# coil_processing.net
KiCad netlist of a schematic drawn in Altium Designer
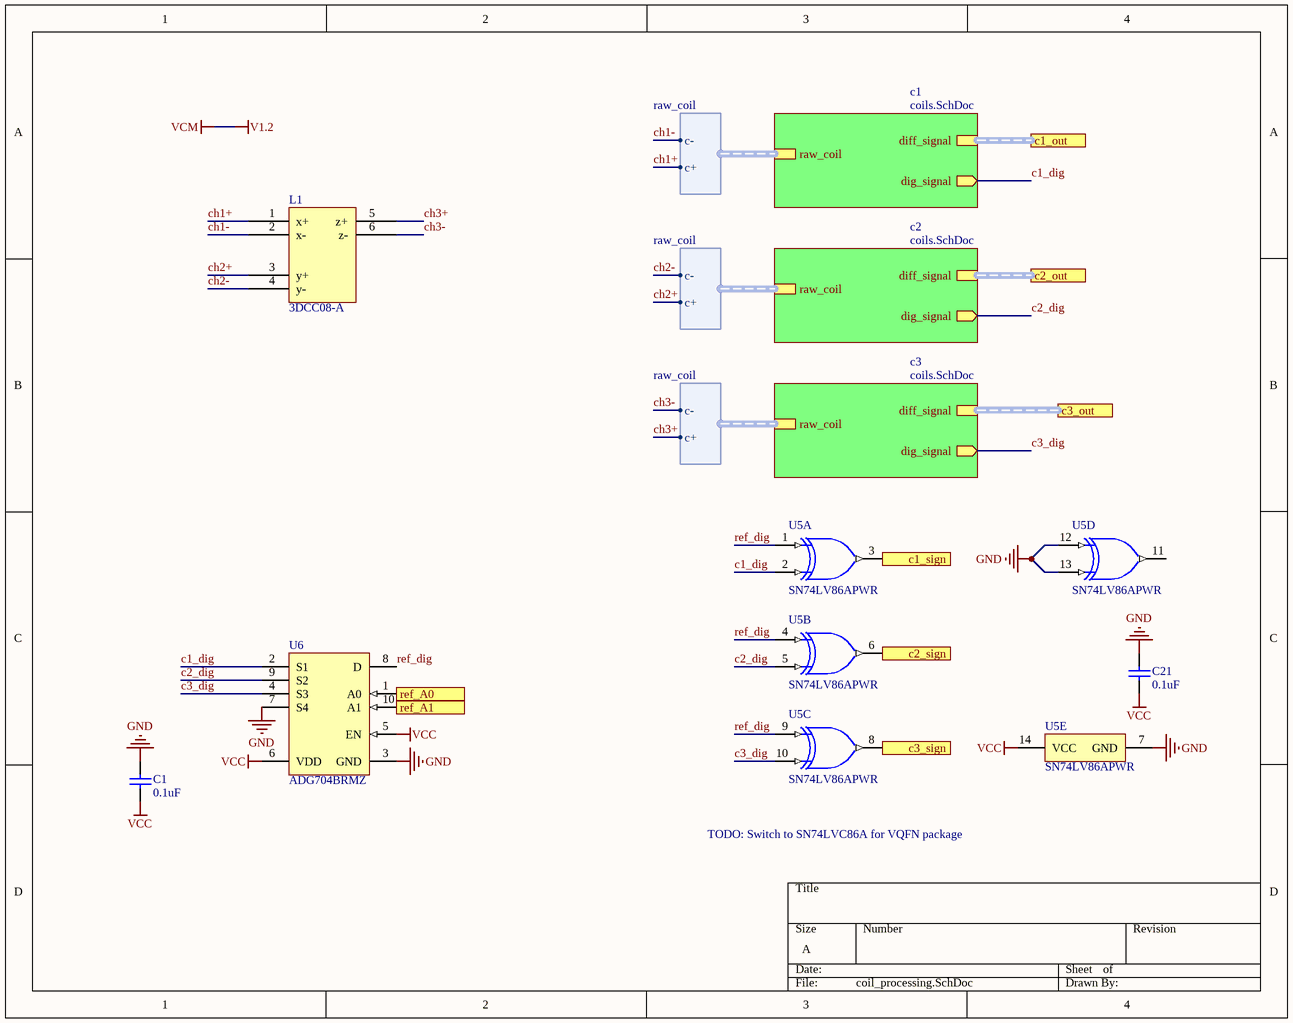
[diagram p0: coil_processing.SchDoc]

(export (version "E")
  (design (tool "Eeschema 10.0.6"))
  (components
    (comp (ref "C1")
      (value "0.1uF")
      (footprint "0402")
      (description "Ceramic Capacitor (Surface Mount)")
      (fields (field (name "MANUFACTURER") "Generic Ceramic Chip Cap (TBD)") (field (name "Comment") "Cap"))
      (libsource (lib "maglib") (part "Cap"))
    )
    (comp (ref "C21")
      (value "0.1uF")
      (footprint "0402")
      (description "Ceramic Capacitor (Surface Mount)")
      (fields (field (name "MANUFACTURER") "Generic Ceramic Chip Cap (TBD)") (field (name "Comment") "Cap"))
      (libsource (lib "maglib") (part "Cap"))
    )
    (comp (ref "L1") (value "3DCC08-A") (footprint "3DCC08-A") (libsource (lib "maglib") (part "3DCC08-A")))
    (comp (ref "U5")
      (value "SN74LV86APWR")
      (footprint "PW0014A_L")
      (description "Quadruple 2-Input Exclusive-OR Gates, PW0014A, LARGE T&R")
      (fields
        (field (name "GENERIC PART NUMBER") "SN74LV86A")
        (field (name "MANUFACTURER") "Texas Instruments")
      )
      (libsource (lib "Altium Content Vault") (part "TI-XOR-4-2IN-14"))
    )
    (comp (ref "U6")
      (value "ADG704BRMZ")
      (footprint "ADI-RM-10_N")
      (description "CMOS Low Voltage 4 Ohm, 4-Channel Multiplexer, -40 to 85 degC, 10-pin SOP (RM-10), Tube")
      (fields (field (name "MANUFACTURER") "Analog Devices"))
      (libsource (lib "Altium Content Vault") (part "ADI-ADG704-RM-10"))
    )
  )
  (nets
    (net (code "5") (name "/c1_dig") (class "Default")
      (node (ref "U5") (pin "2") (pinfunction "1B_2") (pintype "input"))
      (node (ref "U6") (pin "2") (pinfunction "S1_2") (pintype "passive"))
    )
    (net (code "7") (name "/c1_sign") (class "Default")
      (node (ref "U5") (pin "3") (pinfunction "1Y_3") (pintype "output"))
    )
    (net (code "8") (name "/c2_dig") (class "Default")
      (node (ref "U5") (pin "5") (pinfunction "2B_5") (pintype "input"))
      (node (ref "U6") (pin "9") (pinfunction "S2_9") (pintype "passive"))
    )
    (net (code "10") (name "/c2_sign") (class "Default")
      (node (ref "U5") (pin "6") (pinfunction "2Y_6") (pintype "output"))
    )
    (net (code "11") (name "/c3_dig") (class "Default")
      (node (ref "U5") (pin "10") (pinfunction "3B_10") (pintype "input"))
      (node (ref "U6") (pin "4") (pinfunction "S3_4") (pintype "passive"))
    )
    (net (code "13") (name "/c3_sign") (class "Default")
      (node (ref "U5") (pin "8") (pinfunction "3Y_8") (pintype "output"))
    )
    (net (code "14") (name "/ch1+") (class "Default")
      (node (ref "L1") (pin "1") (pinfunction "x+_1") (pintype "passive"))
    )
    (net (code "15") (name "/ch1-") (class "Default")
      (node (ref "L1") (pin "2") (pinfunction "x-_2") (pintype "passive"))
    )
    (net (code "16") (name "/ch2+") (class "Default")
      (node (ref "L1") (pin "3") (pinfunction "y+_3") (pintype "passive"))
    )
    (net (code "17") (name "/ch2-") (class "Default")
      (node (ref "L1") (pin "4") (pinfunction "y-_4") (pintype "passive"))
    )
    (net (code "18") (name "/ch3+") (class "Default")
      (node (ref "L1") (pin "5") (pinfunction "z+_5") (pintype "passive"))
    )
    (net (code "19") (name "/ch3-") (class "Default")
      (node (ref "L1") (pin "6") (pinfunction "z-_6") (pintype "passive"))
    )
    (net (code "20") (name "/ref_A0") (class "Default")
      (node (ref "U6") (pin "1") (pinfunction "A0_1") (pintype "input"))
    )
    (net (code "21") (name "/ref_A1") (class "Default")
      (node (ref "U6") (pin "10") (pinfunction "A1_10") (pintype "input"))
    )
    (net (code "22") (name "/ref_dig") (class "Default")
      (node (ref "U5") (pin "1") (pinfunction "1A_1") (pintype "input"))
      (node (ref "U5") (pin "4") (pinfunction "2A_4") (pintype "input"))
      (node (ref "U5") (pin "9") (pinfunction "3A_9") (pintype "input"))
      (node (ref "U6") (pin "8") (pinfunction "D_8") (pintype "passive"))
    )
    (net (code "24") (name "GND") (class "Default")
      (node (ref "C1") (pin "2") (pinfunction "2_2") (pintype "passive"))
      (node (ref "C21") (pin "2") (pinfunction "2_2") (pintype "passive"))
      (node (ref "U5") (pin "12") (pinfunction "4A_12") (pintype "input"))
      (node (ref "U5") (pin "13") (pinfunction "4B_13") (pintype "input"))
      (node (ref "U5") (pin "7") (pinfunction "GND_7") (pintype "power_in"))
      (node (ref "U6") (pin "3") (pinfunction "GND_3") (pintype "power_in"))
      (node (ref "U6") (pin "7") (pinfunction "S4_7") (pintype "passive"))
    )
    (net (code "26") (name "VCC") (class "Default")
      (node (ref "C1") (pin "1") (pinfunction "1_1") (pintype "passive"))
      (node (ref "C21") (pin "1") (pinfunction "1_1") (pintype "passive"))
      (node (ref "U5") (pin "14") (pinfunction "VCC_14") (pintype "power_in"))
      (node (ref "U6") (pin "5") (pinfunction "EN_5") (pintype "input"))
      (node (ref "U6") (pin "6") (pinfunction "VDD_6") (pintype "power_in"))
    )
    (net (code "27") (name "unconnected-(U5D-4Y-Pad11)") (class "Default")
      (node (ref "U5") (pin "11") (pinfunction "4Y_11") (pintype "output"))
    )
  )
)
